# Adapter-CMRI8-RJ45.net
KiCad netlist of a schematic drawn in EAGLE
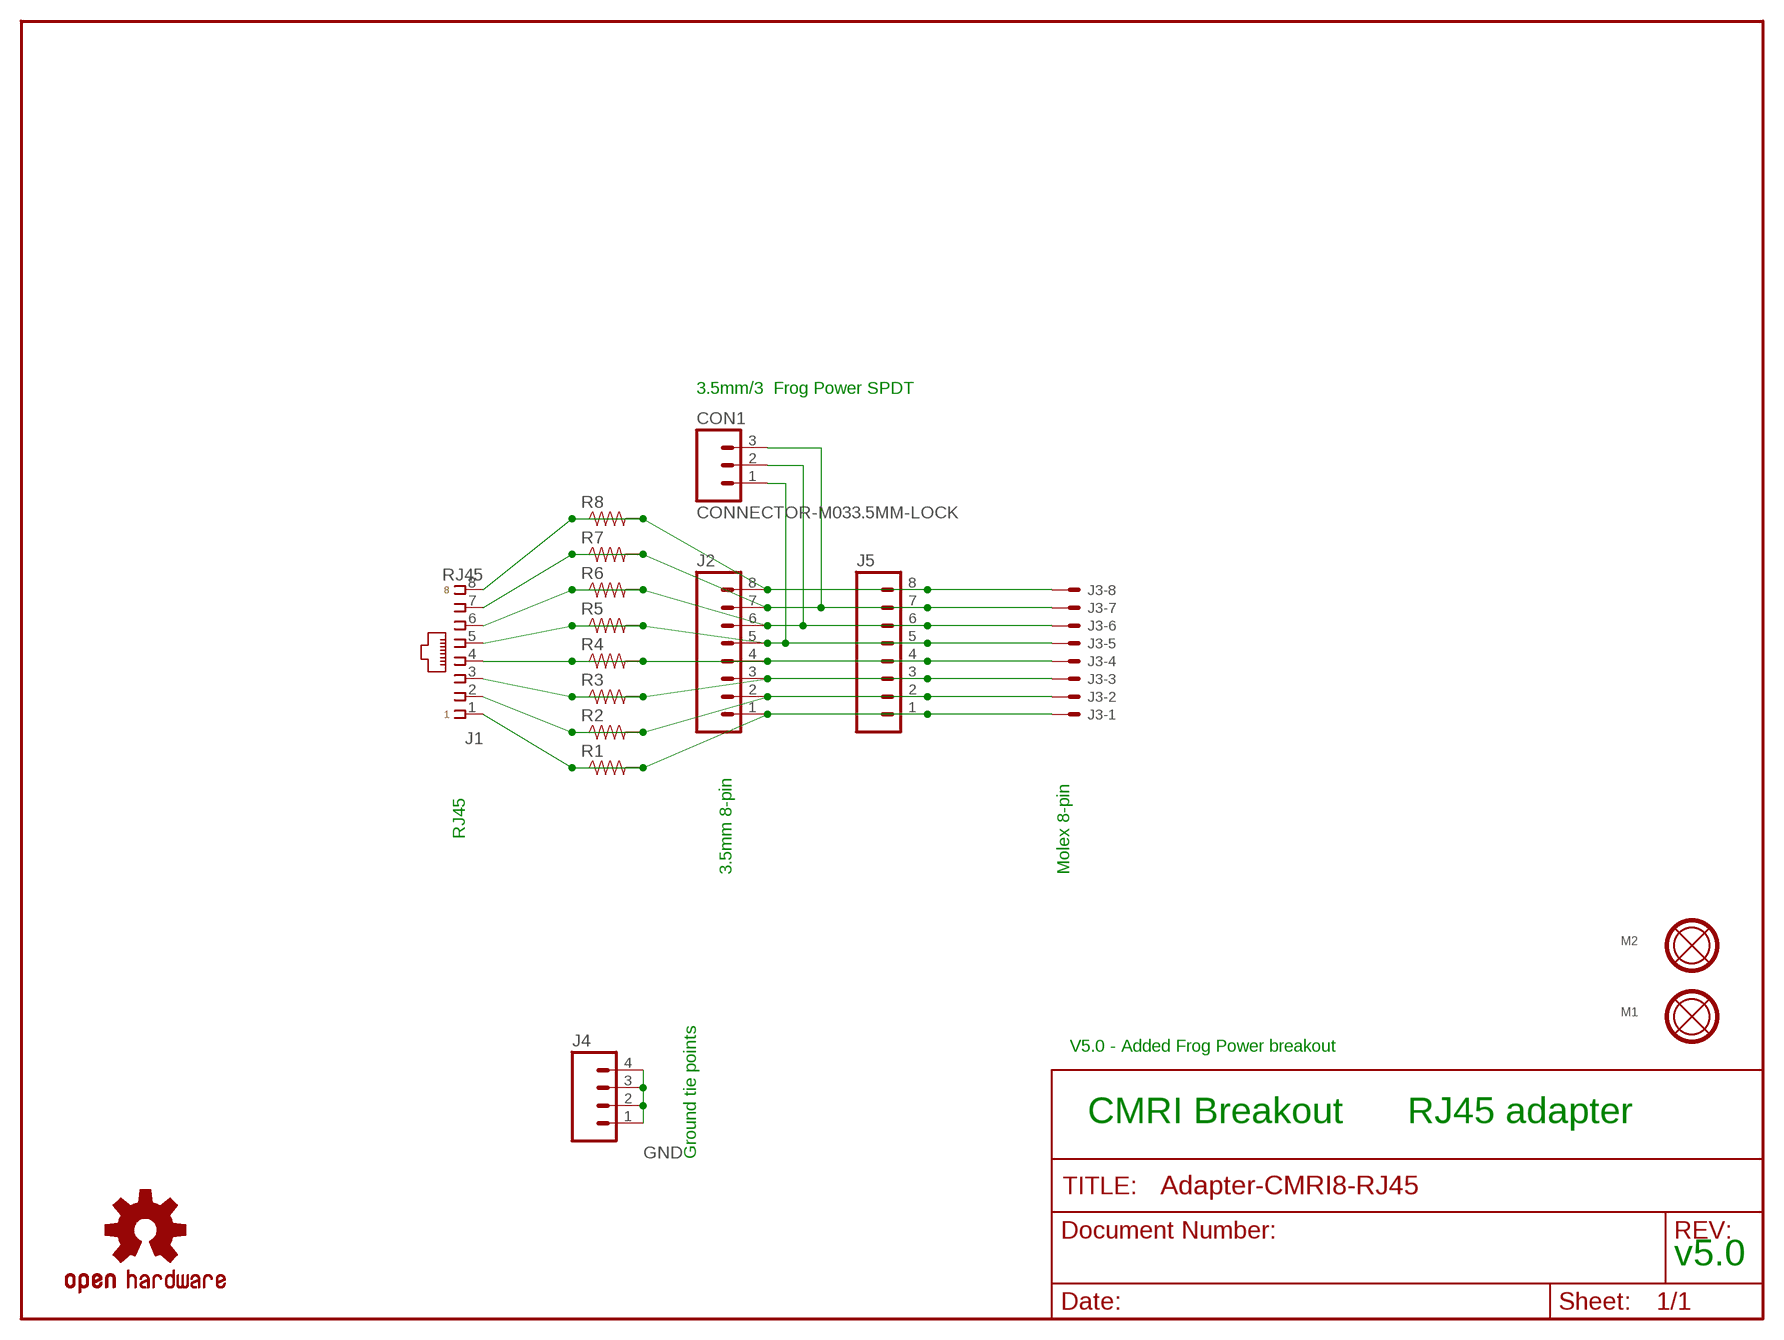
[diagram p0: schematic, sheet 1]

(export (version "E")
  (design (tool "Eeschema 10.0.6"))
  (components
    (comp (ref "CON1")
      (value "CONNECTOR-M033.5MM-LOCK")
      (footprint "eagle-import:SCREWTERMINAL-3.5MM-3_LOCK.007S")
      (libsource (lib "eagle-import") (part "CONNECTOR-M033.5MM-LOCK"))
    )
    (comp (ref "J1")
      (value "RJ45")
      (footprint "eagle-import:RJ45-NO-SHIELD")
      (libsource (lib "eagle-import") (part "CONNECTOR-RJ45-FRONT"))
    )
    (comp (ref "J2")
      (value "CONNECTOR-M083.5MM-8")
      (footprint "eagle-import:SCREWTERMINAL-3.5MM-8")
      (libsource (lib "eagle-import") (part "CONNECTOR-M083.5MM-8"))
    )
    (comp (ref "J3")
      (value "KK-156-8F")
      (footprint "eagle-import:KK-156-8-F")
      (libsource (lib "eagle-import") (part "KK-156-8F"))
    )
    (comp (ref "J4")
      (value "CONNECTOR-M04SCREW_LOCK")
      (footprint "eagle-import:SCREWTERMINAL-3.5MM-4_LOCK")
      (libsource (lib "eagle-import") (part "CONNECTOR-M04SCREW_LOCK"))
    )
    (comp (ref "J5")
      (value "CONNECTOR-M08LOCK")
      (footprint "eagle-import:1X08_LOCK")
      (libsource (lib "eagle-import") (part "CONNECTOR-M08LOCK"))
    )
    (comp (ref "M1")
      (value "MOUNTINGHOLE")
      (footprint "eagle-import:MOUNTINGHOLE")
      (libsource (lib "eagle-import") (part "MOUNTINGHOLE"))
    )
    (comp (ref "M2")
      (value "MOUNTINGHOLE")
      (footprint "eagle-import:MOUNTINGHOLE")
      (libsource (lib "eagle-import") (part "MOUNTINGHOLE"))
    )
    (comp (ref "R1")
      (value "RPTH04")
      (footprint "eagle-import:AXIAL-0.4-RES")
      (libsource (lib "eagle-import") (part "RPTH04"))
    )
    (comp (ref "R2")
      (value "RPTH04")
      (footprint "eagle-import:AXIAL-0.4-RES")
      (libsource (lib "eagle-import") (part "RPTH04"))
    )
    (comp (ref "R3")
      (value "RPTH04")
      (footprint "eagle-import:AXIAL-0.4-RES")
      (libsource (lib "eagle-import") (part "RPTH04"))
    )
    (comp (ref "R4")
      (value "RPTH04")
      (footprint "eagle-import:AXIAL-0.4-RES")
      (libsource (lib "eagle-import") (part "RPTH04"))
    )
    (comp (ref "R5")
      (value "RPTH04")
      (footprint "eagle-import:AXIAL-0.4-RES")
      (libsource (lib "eagle-import") (part "RPTH04"))
    )
    (comp (ref "R6")
      (value "RPTH04")
      (footprint "eagle-import:AXIAL-0.4-RES")
      (libsource (lib "eagle-import") (part "RPTH04"))
    )
    (comp (ref "R7")
      (value "RPTH04")
      (footprint "eagle-import:AXIAL-0.4-RES")
      (libsource (lib "eagle-import") (part "RPTH04"))
    )
    (comp (ref "R8")
      (value "RPTH04")
      (footprint "eagle-import:AXIAL-0.4-RES")
      (libsource (lib "eagle-import") (part "RPTH04"))
    )
    (comp (ref "U$1")
      (value "DOC-OSHW-LOGO-L")
      (footprint "eagle-import:OSHW-LOGO-L")
      (libsource (lib "eagle-import") (part "DOC-OSHW-LOGO-L"))
    )
  )
  (nets
    (net (code "1") (name "/GND") (class "Default")
      (node (ref "J4") (pin "1") (pinfunction "1_1") (pintype "passive"))
      (node (ref "J4") (pin "2") (pinfunction "2_2") (pintype "passive"))
      (node (ref "J4") (pin "3") (pinfunction "3_3") (pintype "passive"))
      (node (ref "J4") (pin "4") (pinfunction "4_4") (pintype "passive"))
    )
    (net (code "2") (name "Net-(J3A-S)") (class "Default")
      (node (ref "J1") (pin "1") (pinfunction "1_1") (pintype "passive"))
      (node (ref "J2") (pin "1") (pinfunction "1_1") (pintype "passive"))
      (node (ref "J3") (pin "1") (pinfunction "S_1") (pintype "passive"))
      (node (ref "J5") (pin "1") (pinfunction "1_1") (pintype "passive"))
      (node (ref "R1") (pin "P$1") (pinfunction "1_P$1") (pintype "passive"))
      (node (ref "R1") (pin "P$2") (pinfunction "2_P$2") (pintype "passive"))
    )
    (net (code "3") (name "Net-(J3B-S)") (class "Default")
      (node (ref "J1") (pin "2") (pinfunction "2_2") (pintype "passive"))
      (node (ref "J2") (pin "2") (pinfunction "2_2") (pintype "passive"))
      (node (ref "J3") (pin "2") (pinfunction "S_2") (pintype "passive"))
      (node (ref "J5") (pin "2") (pinfunction "2_2") (pintype "passive"))
      (node (ref "R2") (pin "P$1") (pinfunction "1_P$1") (pintype "passive"))
      (node (ref "R2") (pin "P$2") (pinfunction "2_P$2") (pintype "passive"))
    )
    (net (code "4") (name "Net-(J3C-S)") (class "Default")
      (node (ref "J1") (pin "3") (pinfunction "3_3") (pintype "passive"))
      (node (ref "J2") (pin "3") (pinfunction "3_3") (pintype "passive"))
      (node (ref "J3") (pin "3") (pinfunction "S_3") (pintype "passive"))
      (node (ref "J5") (pin "3") (pinfunction "3_3") (pintype "passive"))
      (node (ref "R3") (pin "P$1") (pinfunction "1_P$1") (pintype "passive"))
      (node (ref "R3") (pin "P$2") (pinfunction "2_P$2") (pintype "passive"))
    )
    (net (code "5") (name "Net-(J3D-S)") (class "Default")
      (node (ref "J1") (pin "4") (pinfunction "4_4") (pintype "passive"))
      (node (ref "J2") (pin "4") (pinfunction "4_4") (pintype "passive"))
      (node (ref "J3") (pin "4") (pinfunction "S_4") (pintype "passive"))
      (node (ref "J5") (pin "4") (pinfunction "4_4") (pintype "passive"))
      (node (ref "R4") (pin "P$1") (pinfunction "1_P$1") (pintype "passive"))
      (node (ref "R4") (pin "P$2") (pinfunction "2_P$2") (pintype "passive"))
    )
    (net (code "6") (name "Net-(J3E-S)") (class "Default")
      (node (ref "CON1") (pin "1") (pinfunction "1_1") (pintype "passive"))
      (node (ref "J1") (pin "5") (pinfunction "5_5") (pintype "passive"))
      (node (ref "J2") (pin "5") (pinfunction "5_5") (pintype "passive"))
      (node (ref "J3") (pin "5") (pinfunction "S_5") (pintype "passive"))
      (node (ref "J5") (pin "5") (pinfunction "5_5") (pintype "passive"))
      (node (ref "R5") (pin "P$1") (pinfunction "1_P$1") (pintype "passive"))
      (node (ref "R5") (pin "P$2") (pinfunction "2_P$2") (pintype "passive"))
    )
    (net (code "7") (name "Net-(J3F-S)") (class "Default")
      (node (ref "CON1") (pin "2") (pinfunction "2_2") (pintype "passive"))
      (node (ref "J1") (pin "6") (pinfunction "6_6") (pintype "passive"))
      (node (ref "J2") (pin "6") (pinfunction "6_6") (pintype "passive"))
      (node (ref "J3") (pin "6") (pinfunction "S_6") (pintype "passive"))
      (node (ref "J5") (pin "6") (pinfunction "6_6") (pintype "passive"))
      (node (ref "R6") (pin "P$1") (pinfunction "1_P$1") (pintype "passive"))
      (node (ref "R6") (pin "P$2") (pinfunction "2_P$2") (pintype "passive"))
    )
    (net (code "8") (name "Net-(J3G-S)") (class "Default")
      (node (ref "CON1") (pin "3") (pinfunction "3_3") (pintype "passive"))
      (node (ref "J1") (pin "7") (pinfunction "7_7") (pintype "passive"))
      (node (ref "J2") (pin "7") (pinfunction "7_7") (pintype "passive"))
      (node (ref "J3") (pin "7") (pinfunction "S_7") (pintype "passive"))
      (node (ref "J5") (pin "7") (pinfunction "7_7") (pintype "passive"))
      (node (ref "R7") (pin "P$1") (pinfunction "1_P$1") (pintype "passive"))
      (node (ref "R7") (pin "P$2") (pinfunction "2_P$2") (pintype "passive"))
    )
    (net (code "9") (name "Net-(J3H-S)") (class "Default")
      (node (ref "J1") (pin "8") (pinfunction "8_8") (pintype "passive"))
      (node (ref "J2") (pin "8") (pinfunction "8_8") (pintype "passive"))
      (node (ref "J3") (pin "8") (pinfunction "S_8") (pintype "passive"))
      (node (ref "J5") (pin "8") (pinfunction "8_8") (pintype "passive"))
      (node (ref "R8") (pin "P$1") (pinfunction "1_P$1") (pintype "passive"))
      (node (ref "R8") (pin "P$2") (pinfunction "2_P$2") (pintype "passive"))
    )
  )
)
